# ArduinoMega.net
KiCad netlist of a schematic drawn in Altium Designer
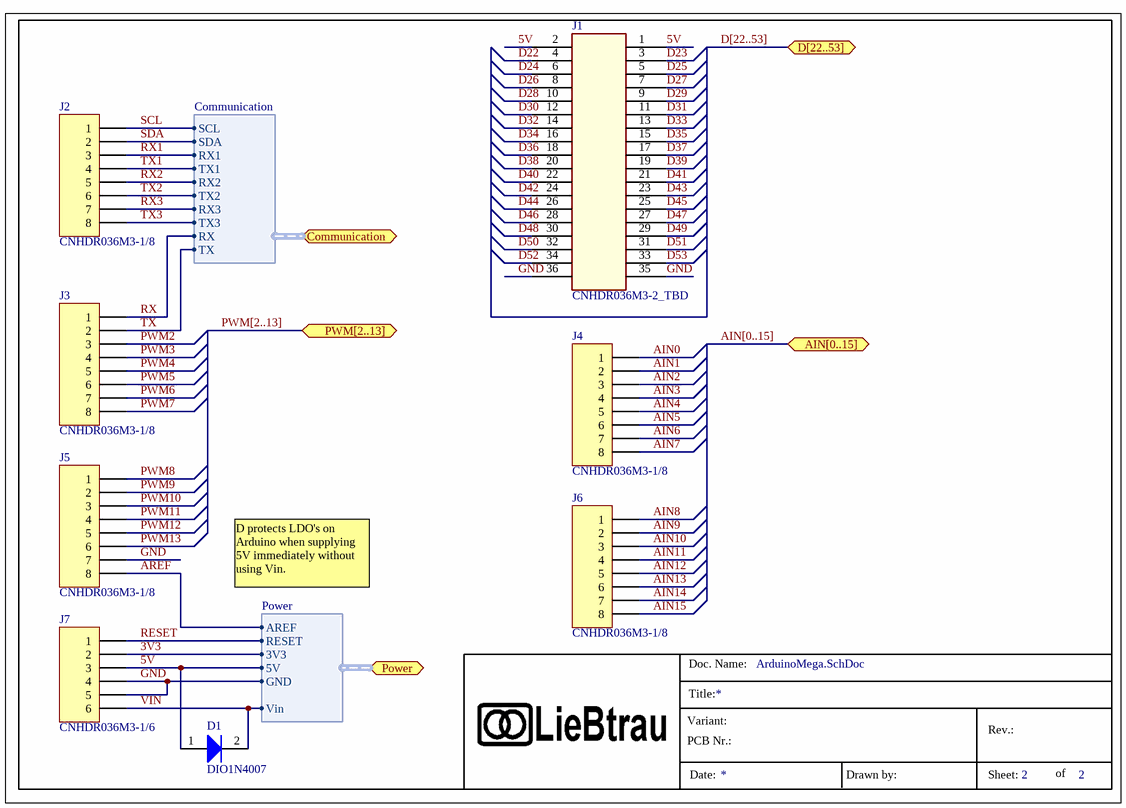
[diagram p0: ArduinoMega.SchDoc]

(export (version "E")
  (design (tool "Eeschema 10.0.6"))
  (components
    (comp (ref "D1")
      (value "DIO1N4007")
      (footprint "DO-41")
      (description "1 Amp General Purpose Rectifier")
      (libsource (lib "Testing") (part "D_DIODE"))
    )
    (comp (ref "J1")
      (value "CNHDR036M3-2_TBD")
      (footprint "J_HDR2X18")
      (libsource (lib "Testing") (part "J_2X18P"))
    )
    (comp (ref "J2")
      (value "CNHDR036M3-1/8")
      (footprint "J_HDR1X8")
      (libsource (lib "Testing") (part "J_8P"))
    )
    (comp (ref "J3")
      (value "CNHDR036M3-1/8")
      (footprint "J_HDR1X8")
      (libsource (lib "Testing") (part "J_8P"))
    )
    (comp (ref "J4")
      (value "CNHDR036M3-1/8")
      (footprint "J_HDR1X8")
      (libsource (lib "Testing") (part "J_8P"))
    )
    (comp (ref "J5")
      (value "CNHDR036M3-1/8")
      (footprint "J_HDR1X8")
      (libsource (lib "Testing") (part "J_8P"))
    )
    (comp (ref "J6")
      (value "CNHDR036M3-1/8")
      (footprint "J_HDR1X8")
      (libsource (lib "Testing") (part "J_8P"))
    )
    (comp (ref "J7")
      (value "CNHDR036M3-1/6")
      (footprint "J_HDR1X6")
      (libsource (lib "Testing") (part "J_6P"))
    )
  )
  (nets
    (net (code "3") (name "/3V3") (class "Default")
      (node (ref "J7") (pin "2") (pinfunction "2_2") (pintype "passive"))
    )
    (net (code "4") (name "/5V") (class "Default")
      (node (ref "D1") (pin "1") (pinfunction "A_1") (pintype "passive"))
      (node (ref "J1") (pin "1") (pinfunction "1_1") (pintype "passive"))
      (node (ref "J1") (pin "2") (pinfunction "2_2") (pintype "passive"))
      (node (ref "J7") (pin "3") (pinfunction "3_3") (pintype "passive"))
    )
    (net (code "5") (name "/AIN0") (class "Default")
      (node (ref "J4") (pin "1") (pinfunction "1_1") (pintype "passive"))
    )
    (net (code "6") (name "/AIN1") (class "Default")
      (node (ref "J4") (pin "2") (pinfunction "2_2") (pintype "passive"))
    )
    (net (code "7") (name "/AIN2") (class "Default")
      (node (ref "J4") (pin "3") (pinfunction "3_3") (pintype "passive"))
    )
    (net (code "8") (name "/AIN3") (class "Default")
      (node (ref "J4") (pin "4") (pinfunction "4_4") (pintype "passive"))
    )
    (net (code "9") (name "/AIN4") (class "Default")
      (node (ref "J4") (pin "5") (pinfunction "5_5") (pintype "passive"))
    )
    (net (code "10") (name "/AIN5") (class "Default")
      (node (ref "J4") (pin "6") (pinfunction "6_6") (pintype "passive"))
    )
    (net (code "11") (name "/AIN6") (class "Default")
      (node (ref "J4") (pin "7") (pinfunction "7_7") (pintype "passive"))
    )
    (net (code "12") (name "/AIN7") (class "Default")
      (node (ref "J4") (pin "8") (pinfunction "8_8") (pintype "passive"))
    )
    (net (code "13") (name "/AIN8") (class "Default")
      (node (ref "J6") (pin "1") (pinfunction "1_1") (pintype "passive"))
    )
    (net (code "14") (name "/AIN9") (class "Default")
      (node (ref "J6") (pin "2") (pinfunction "2_2") (pintype "passive"))
    )
    (net (code "15") (name "/AIN10") (class "Default")
      (node (ref "J6") (pin "3") (pinfunction "3_3") (pintype "passive"))
    )
    (net (code "16") (name "/AIN11") (class "Default")
      (node (ref "J6") (pin "4") (pinfunction "4_4") (pintype "passive"))
    )
    (net (code "17") (name "/AIN12") (class "Default")
      (node (ref "J6") (pin "5") (pinfunction "5_5") (pintype "passive"))
    )
    (net (code "18") (name "/AIN13") (class "Default")
      (node (ref "J6") (pin "6") (pinfunction "6_6") (pintype "passive"))
    )
    (net (code "19") (name "/AIN14") (class "Default")
      (node (ref "J6") (pin "7") (pinfunction "7_7") (pintype "passive"))
    )
    (net (code "20") (name "/AIN15") (class "Default")
      (node (ref "J6") (pin "8") (pinfunction "8_8") (pintype "passive"))
    )
    (net (code "22") (name "/AREF") (class "Default")
      (node (ref "J5") (pin "8") (pinfunction "8_8") (pintype "passive"))
    )
    (net (code "23") (name "/D22") (class "Default")
      (node (ref "J1") (pin "4") (pinfunction "4_4") (pintype "passive"))
    )
    (net (code "24") (name "/D23") (class "Default")
      (node (ref "J1") (pin "3") (pinfunction "3_3") (pintype "passive"))
    )
    (net (code "25") (name "/D24") (class "Default")
      (node (ref "J1") (pin "6") (pinfunction "6_6") (pintype "passive"))
    )
    (net (code "26") (name "/D25") (class "Default")
      (node (ref "J1") (pin "5") (pinfunction "5_5") (pintype "passive"))
    )
    (net (code "27") (name "/D26") (class "Default")
      (node (ref "J1") (pin "8") (pinfunction "8_8") (pintype "passive"))
    )
    (net (code "28") (name "/D27") (class "Default")
      (node (ref "J1") (pin "7") (pinfunction "7_7") (pintype "passive"))
    )
    (net (code "29") (name "/D28") (class "Default")
      (node (ref "J1") (pin "10") (pinfunction "10_10") (pintype "passive"))
    )
    (net (code "30") (name "/D29") (class "Default")
      (node (ref "J1") (pin "9") (pinfunction "9_9") (pintype "passive"))
    )
    (net (code "31") (name "/D30") (class "Default")
      (node (ref "J1") (pin "12") (pinfunction "12_12") (pintype "passive"))
    )
    (net (code "32") (name "/D31") (class "Default")
      (node (ref "J1") (pin "11") (pinfunction "11_11") (pintype "passive"))
    )
    (net (code "33") (name "/D32") (class "Default")
      (node (ref "J1") (pin "14") (pinfunction "14_14") (pintype "passive"))
    )
    (net (code "34") (name "/D33") (class "Default")
      (node (ref "J1") (pin "13") (pinfunction "13_13") (pintype "passive"))
    )
    (net (code "35") (name "/D34") (class "Default")
      (node (ref "J1") (pin "16") (pinfunction "16_16") (pintype "passive"))
    )
    (net (code "36") (name "/D35") (class "Default")
      (node (ref "J1") (pin "15") (pinfunction "15_15") (pintype "passive"))
    )
    (net (code "37") (name "/D36") (class "Default")
      (node (ref "J1") (pin "18") (pinfunction "18_18") (pintype "passive"))
    )
    (net (code "38") (name "/D37") (class "Default")
      (node (ref "J1") (pin "17") (pinfunction "17_17") (pintype "passive"))
    )
    (net (code "39") (name "/D38") (class "Default")
      (node (ref "J1") (pin "20") (pinfunction "20_20") (pintype "passive"))
    )
    (net (code "40") (name "/D39") (class "Default")
      (node (ref "J1") (pin "19") (pinfunction "19_19") (pintype "passive"))
    )
    (net (code "41") (name "/D40") (class "Default")
      (node (ref "J1") (pin "22") (pinfunction "22_22") (pintype "passive"))
    )
    (net (code "42") (name "/D41") (class "Default")
      (node (ref "J1") (pin "21") (pinfunction "21_21") (pintype "passive"))
    )
    (net (code "43") (name "/D42") (class "Default")
      (node (ref "J1") (pin "24") (pinfunction "24_24") (pintype "passive"))
    )
    (net (code "44") (name "/D43") (class "Default")
      (node (ref "J1") (pin "23") (pinfunction "23_23") (pintype "passive"))
    )
    (net (code "45") (name "/D44") (class "Default")
      (node (ref "J1") (pin "26") (pinfunction "26_26") (pintype "passive"))
    )
    (net (code "46") (name "/D45") (class "Default")
      (node (ref "J1") (pin "25") (pinfunction "25_25") (pintype "passive"))
    )
    (net (code "47") (name "/D46") (class "Default")
      (node (ref "J1") (pin "28") (pinfunction "28_28") (pintype "passive"))
    )
    (net (code "48") (name "/D47") (class "Default")
      (node (ref "J1") (pin "27") (pinfunction "27_27") (pintype "passive"))
    )
    (net (code "49") (name "/D48") (class "Default")
      (node (ref "J1") (pin "30") (pinfunction "30_30") (pintype "passive"))
    )
    (net (code "50") (name "/D49") (class "Default")
      (node (ref "J1") (pin "29") (pinfunction "29_29") (pintype "passive"))
    )
    (net (code "51") (name "/D50") (class "Default")
      (node (ref "J1") (pin "32") (pinfunction "32_32") (pintype "passive"))
    )
    (net (code "52") (name "/D51") (class "Default")
      (node (ref "J1") (pin "31") (pinfunction "31_31") (pintype "passive"))
    )
    (net (code "53") (name "/D52") (class "Default")
      (node (ref "J1") (pin "34") (pinfunction "34_34") (pintype "passive"))
    )
    (net (code "54") (name "/D53") (class "Default")
      (node (ref "J1") (pin "33") (pinfunction "33_33") (pintype "passive"))
    )
    (net (code "56") (name "/GND") (class "Default")
      (node (ref "J1") (pin "35") (pinfunction "35_35") (pintype "passive"))
      (node (ref "J1") (pin "36") (pinfunction "36_36") (pintype "passive"))
      (node (ref "J5") (pin "7") (pinfunction "7_7") (pintype "passive"))
      (node (ref "J7") (pin "4") (pinfunction "4_4") (pintype "passive"))
      (node (ref "J7") (pin "5") (pinfunction "5_5") (pintype "passive"))
    )
    (net (code "57") (name "/PWM2") (class "Default")
      (node (ref "J3") (pin "3") (pinfunction "3_3") (pintype "passive"))
    )
    (net (code "58") (name "/PWM3") (class "Default")
      (node (ref "J3") (pin "4") (pinfunction "4_4") (pintype "passive"))
    )
    (net (code "59") (name "/PWM4") (class "Default")
      (node (ref "J3") (pin "5") (pinfunction "5_5") (pintype "passive"))
    )
    (net (code "60") (name "/PWM5") (class "Default")
      (node (ref "J3") (pin "6") (pinfunction "6_6") (pintype "passive"))
    )
    (net (code "61") (name "/PWM6") (class "Default")
      (node (ref "J3") (pin "7") (pinfunction "7_7") (pintype "passive"))
    )
    (net (code "62") (name "/PWM7") (class "Default")
      (node (ref "J3") (pin "8") (pinfunction "8_8") (pintype "passive"))
    )
    (net (code "63") (name "/PWM8") (class "Default")
      (node (ref "J5") (pin "1") (pinfunction "1_1") (pintype "passive"))
    )
    (net (code "64") (name "/PWM9") (class "Default")
      (node (ref "J5") (pin "2") (pinfunction "2_2") (pintype "passive"))
    )
    (net (code "65") (name "/PWM10") (class "Default")
      (node (ref "J5") (pin "3") (pinfunction "3_3") (pintype "passive"))
    )
    (net (code "66") (name "/PWM11") (class "Default")
      (node (ref "J5") (pin "4") (pinfunction "4_4") (pintype "passive"))
    )
    (net (code "67") (name "/PWM12") (class "Default")
      (node (ref "J5") (pin "5") (pinfunction "5_5") (pintype "passive"))
    )
    (net (code "68") (name "/PWM13") (class "Default")
      (node (ref "J5") (pin "6") (pinfunction "6_6") (pintype "passive"))
    )
    (net (code "70") (name "/RESET") (class "Default")
      (node (ref "J7") (pin "1") (pinfunction "1_1") (pintype "passive"))
    )
    (net (code "71") (name "/RX") (class "Default")
      (node (ref "J3") (pin "1") (pinfunction "1_1") (pintype "passive"))
    )
    (net (code "72") (name "/RX1") (class "Default")
      (node (ref "J2") (pin "3") (pinfunction "3_3") (pintype "passive"))
    )
    (net (code "73") (name "/RX2") (class "Default")
      (node (ref "J2") (pin "5") (pinfunction "5_5") (pintype "passive"))
    )
    (net (code "74") (name "/RX3") (class "Default")
      (node (ref "J2") (pin "7") (pinfunction "7_7") (pintype "passive"))
    )
    (net (code "75") (name "/SCL") (class "Default")
      (node (ref "J2") (pin "1") (pinfunction "1_1") (pintype "passive"))
    )
    (net (code "76") (name "/SDA") (class "Default")
      (node (ref "J2") (pin "2") (pinfunction "2_2") (pintype "passive"))
    )
    (net (code "77") (name "/TX") (class "Default")
      (node (ref "J3") (pin "2") (pinfunction "2_2") (pintype "passive"))
    )
    (net (code "78") (name "/TX1") (class "Default")
      (node (ref "J2") (pin "4") (pinfunction "4_4") (pintype "passive"))
    )
    (net (code "79") (name "/TX2") (class "Default")
      (node (ref "J2") (pin "6") (pinfunction "6_6") (pintype "passive"))
    )
    (net (code "80") (name "/TX3") (class "Default")
      (node (ref "J2") (pin "8") (pinfunction "8_8") (pintype "passive"))
    )
    (net (code "81") (name "/VIN") (class "Default")
      (node (ref "D1") (pin "2") (pinfunction "K_2") (pintype "passive"))
      (node (ref "J7") (pin "6") (pinfunction "6_6") (pintype "passive"))
    )
  )
)
